# fuse-a-1.net
KiCad netlist of a schematic drawn in EAGLE
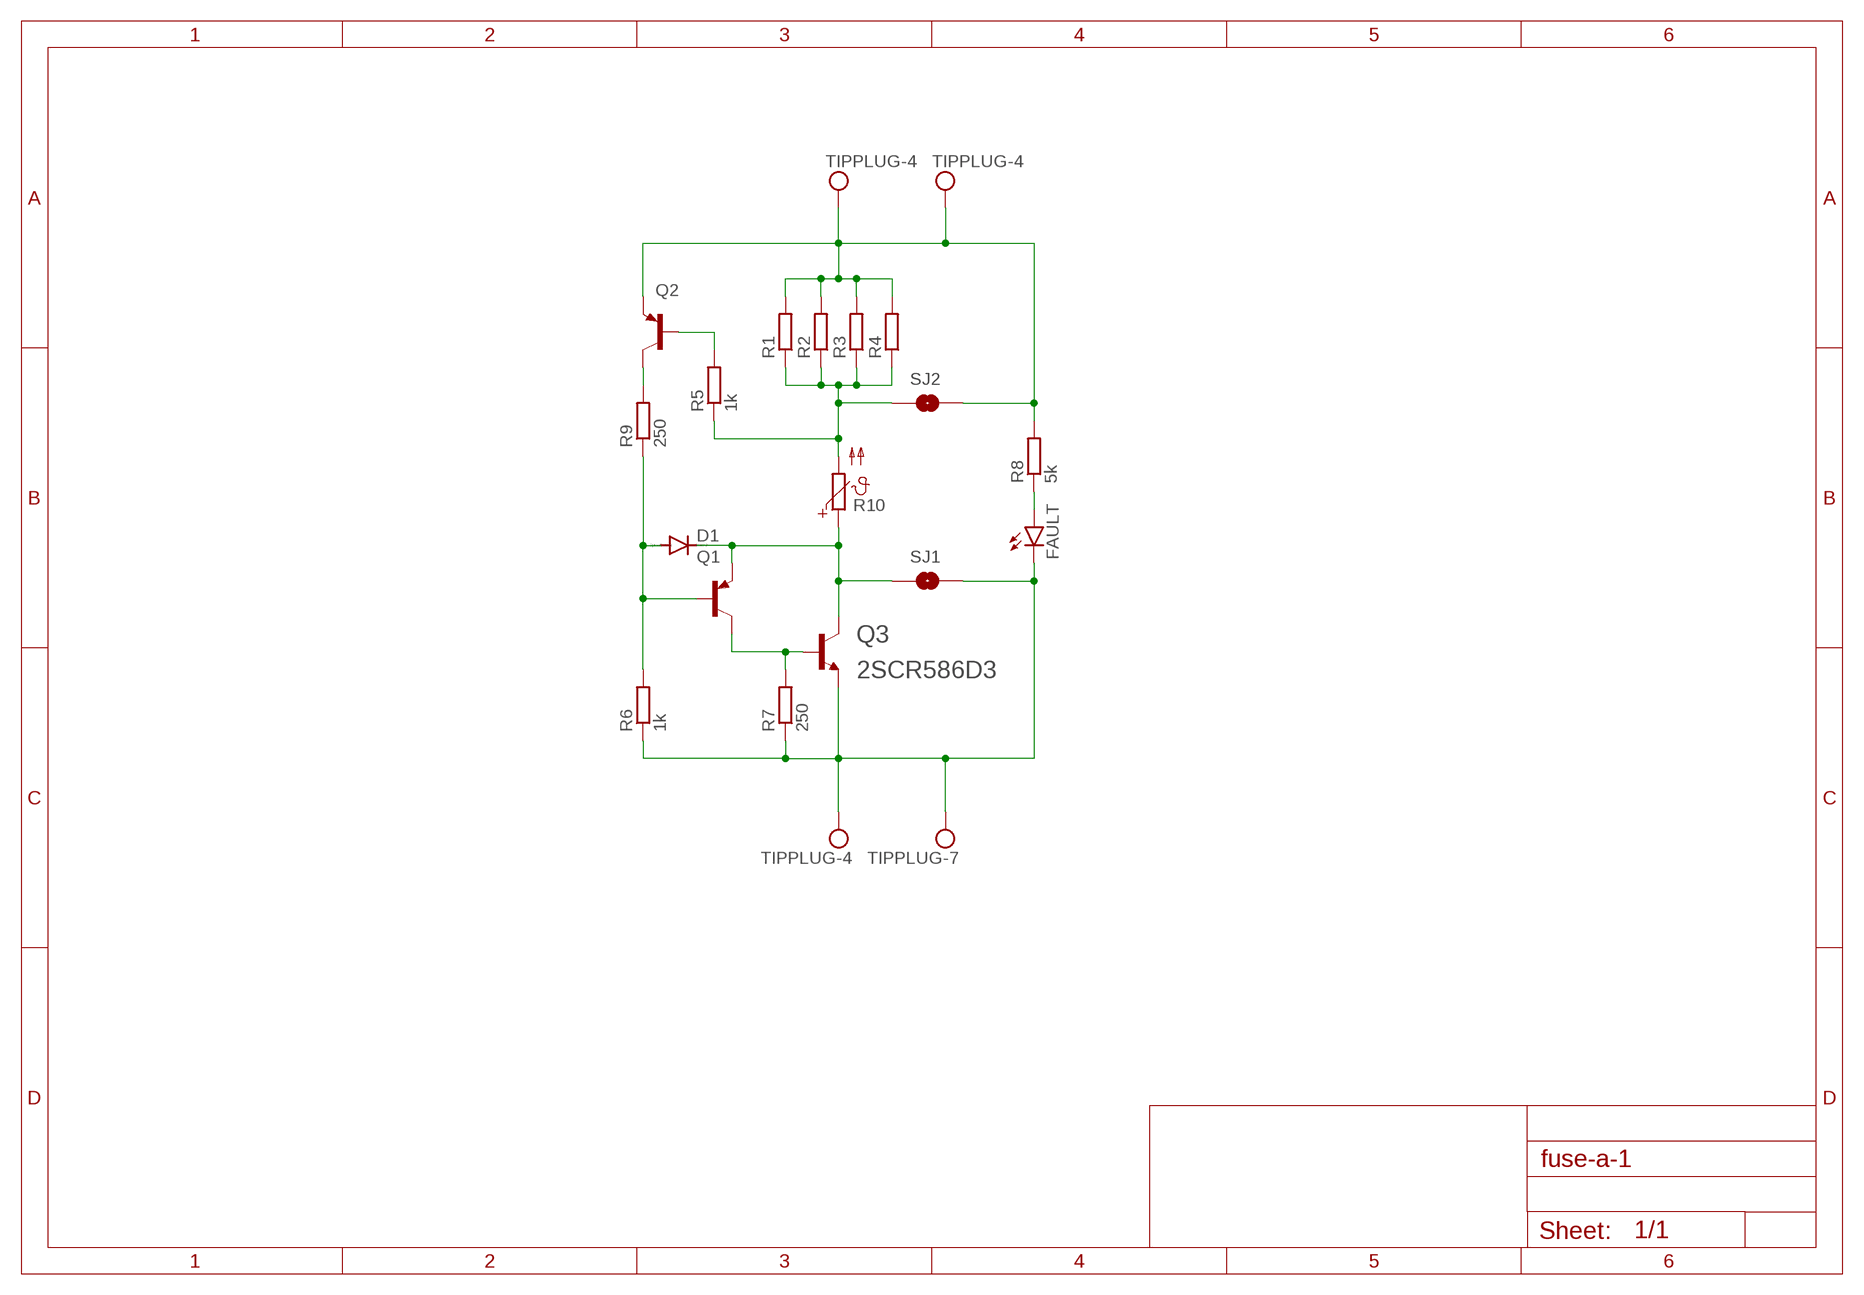
[diagram p0: schematic, sheet 1]

(export (version "E")
  (design (tool "Eeschema 10.0.6"))
  (components
    (comp (ref "D1")
      (value "DIODE-MINIMELF")
      (footprint "eagle-import:MINIMELF")
      (libsource (lib "eagle-import") (part "DIODE-MINIMELF"))
    )
    (comp (ref "FAULT")
      (value "LEDCHIPLED_0603")
      (footprint "eagle-import:CHIPLED_0603")
      (libsource (lib "eagle-import") (part "LEDCHIPLED_0603"))
    )
    (comp (ref "Q1")
      (value "BCX71SMD")
      (footprint "eagle-import:SOT23")
      (libsource (lib "eagle-import") (part "BCX71SMD"))
    )
    (comp (ref "Q2")
      (value "BCX71SMD")
      (footprint "eagle-import:SOT23")
      (libsource (lib "eagle-import") (part "BCX71SMD"))
    )
    (comp (ref "Q3")
      (value "2SCR586D3")
      (footprint "eagle-import:D-PAK_TO252AA")
      (libsource (lib "eagle-import") (part "2SCR586D3TL1"))
    )
    (comp (ref "R1")
      (value "R-EU_R2512")
      (footprint "eagle-import:R2512")
      (libsource (lib "eagle-import") (part "R-EU_R2512"))
    )
    (comp (ref "R2")
      (value "R-EU_R2512")
      (footprint "eagle-import:R2512")
      (libsource (lib "eagle-import") (part "R-EU_R2512"))
    )
    (comp (ref "R3")
      (value "R-EU_R2512")
      (footprint "eagle-import:R2512")
      (libsource (lib "eagle-import") (part "R-EU_R2512"))
    )
    (comp (ref "R4")
      (value "R-EU_R2512")
      (footprint "eagle-import:R2512")
      (libsource (lib "eagle-import") (part "R-EU_R2512"))
    )
    (comp (ref "R5")
      (value "1k")
      (footprint "eagle-import:R0805")
      (libsource (lib "eagle-import") (part "R-EU_R0805"))
    )
    (comp (ref "R6")
      (value "1k")
      (footprint "eagle-import:R0805")
      (libsource (lib "eagle-import") (part "R-EU_R0805"))
    )
    (comp (ref "R7")
      (value "250")
      (footprint "eagle-import:R0805")
      (libsource (lib "eagle-import") (part "R-EU_R0805"))
    )
    (comp (ref "R8")
      (value "5k")
      (footprint "eagle-import:R0805")
      (libsource (lib "eagle-import") (part "R-EU_R0805"))
    )
    (comp (ref "R9")
      (value "250")
      (footprint "eagle-import:R0805")
      (libsource (lib "eagle-import") (part "R-EU_R0805"))
    )
    (comp (ref "R10")
      (value "PTC_1812")
      (footprint "eagle-import:PTC1812")
      (libsource (lib "eagle-import") (part "PTC_1812"))
    )
    (comp (ref "SJ1")
      (value "SJRND2")
      (footprint "eagle-import:SJ_RND2")
      (libsource (lib "eagle-import") (part "SJRND2"))
    )
    (comp (ref "SJ2")
      (value "SJRND2")
      (footprint "eagle-import:SJ_RND2")
      (libsource (lib "eagle-import") (part "SJRND2"))
    )
    (comp (ref "U$1")
      (value "TIPPLUG-4")
      (footprint "eagle-import:BANANAPLUG-4-LUG")
      (libsource (lib "eagle-import") (part "TIPPLUG-4"))
    )
    (comp (ref "U$2")
      (value "TIPPLUG-4")
      (footprint "eagle-import:BANANAPLUG-4-LUG")
      (libsource (lib "eagle-import") (part "TIPPLUG-4"))
    )
    (comp (ref "U$3")
      (value "TIPPLUG-7")
      (footprint "eagle-import:BANANAPLUG-7-LUG")
      (libsource (lib "eagle-import") (part "TIPPLUG-7"))
    )
    (comp (ref "U$4")
      (value "TIPPLUG-4")
      (footprint "eagle-import:BANANAPLUG-4-LUG")
      (libsource (lib "eagle-import") (part "TIPPLUG-4"))
    )
  )
  (nets
    (net (code "1") (name "Net-(FAULT-PadA)") (class "Default")
      (node (ref "FAULT") (pin "A") (pinfunction "A_A") (pintype "passive"))
      (node (ref "R8") (pin "1") (pinfunction "1_1") (pintype "passive"))
    )
    (net (code "2") (name "Net-(Q1-B)") (class "Default")
      (node (ref "D1") (pin "A") (pinfunction "A_A") (pintype "passive"))
      (node (ref "Q1") (pin "1") (pinfunction "B_1") (pintype "passive"))
      (node (ref "R6") (pin "2") (pinfunction "2_2") (pintype "passive"))
      (node (ref "R9") (pin "1") (pinfunction "1_1") (pintype "passive"))
    )
    (net (code "3") (name "Net-(Q1-C)") (class "Default")
      (node (ref "Q1") (pin "3") (pinfunction "C_3") (pintype "passive"))
      (node (ref "Q3") (pin "1") (pinfunction "B_1") (pintype "passive"))
      (node (ref "R7") (pin "2") (pinfunction "2_2") (pintype "passive"))
    )
    (net (code "4") (name "Net-(Q1-E)") (class "Default")
      (node (ref "D1") (pin "C") (pinfunction "C_C") (pintype "passive"))
      (node (ref "Q1") (pin "2") (pinfunction "E_2") (pintype "passive"))
      (node (ref "Q3") (pin "4") (pinfunction "C_4") (pintype "passive"))
      (node (ref "R10") (pin "1") (pinfunction "1_1") (pintype "passive"))
      (node (ref "SJ1") (pin "P$1") (pinfunction "1_P$1") (pintype "passive"))
    )
    (net (code "5") (name "Net-(Q2-B)") (class "Default")
      (node (ref "Q2") (pin "1") (pinfunction "B_1") (pintype "passive"))
      (node (ref "R5") (pin "2") (pinfunction "2_2") (pintype "passive"))
    )
    (net (code "6") (name "Net-(Q2-C)") (class "Default")
      (node (ref "Q2") (pin "3") (pinfunction "C_3") (pintype "passive"))
      (node (ref "R9") (pin "2") (pinfunction "2_2") (pintype "passive"))
    )
    (net (code "7") (name "Net-(Q2-E)") (class "Default")
      (node (ref "Q2") (pin "2") (pinfunction "E_2") (pintype "passive"))
      (node (ref "R1") (pin "2") (pinfunction "2_2") (pintype "passive"))
      (node (ref "R2") (pin "2") (pinfunction "2_2") (pintype "passive"))
      (node (ref "R3") (pin "2") (pinfunction "2_2") (pintype "passive"))
      (node (ref "R4") (pin "2") (pinfunction "2_2") (pintype "passive"))
      (node (ref "R8") (pin "2") (pinfunction "2_2") (pintype "passive"))
      (node (ref "SJ2") (pin "P$2") (pinfunction "2_P$2") (pintype "passive"))
      (node (ref "U$1") (pin "4MM") (pinfunction "$1_4MM") (pintype "passive"))
      (node (ref "U$4") (pin "4MM") (pinfunction "$1_4MM") (pintype "passive"))
    )
    (net (code "8") (name "Net-(Q3-E)") (class "Default")
      (node (ref "FAULT") (pin "C") (pinfunction "C_C") (pintype "passive"))
      (node (ref "Q3") (pin "3") (pinfunction "E_3") (pintype "passive"))
      (node (ref "R6") (pin "1") (pinfunction "1_1") (pintype "passive"))
      (node (ref "R7") (pin "1") (pinfunction "1_1") (pintype "passive"))
      (node (ref "SJ1") (pin "P$2") (pinfunction "2_P$2") (pintype "passive"))
      (node (ref "U$2") (pin "4MM") (pinfunction "$1_4MM") (pintype "passive"))
      (node (ref "U$3") (pin "7MM") (pinfunction "$1_7MM") (pintype "passive"))
    )
    (net (code "9") (name "Net-(SJ2-1)") (class "Default")
      (node (ref "R1") (pin "1") (pinfunction "1_1") (pintype "passive"))
      (node (ref "R10") (pin "2") (pinfunction "2_2") (pintype "passive"))
      (node (ref "R2") (pin "1") (pinfunction "1_1") (pintype "passive"))
      (node (ref "R3") (pin "1") (pinfunction "1_1") (pintype "passive"))
      (node (ref "R4") (pin "1") (pinfunction "1_1") (pintype "passive"))
      (node (ref "R5") (pin "1") (pinfunction "1_1") (pintype "passive"))
      (node (ref "SJ2") (pin "P$1") (pinfunction "1_P$1") (pintype "passive"))
    )
  )
)
